# SCH_batcam10_2026-05-04.net
KiCad netlist of a schematic drawn in EasyEDA
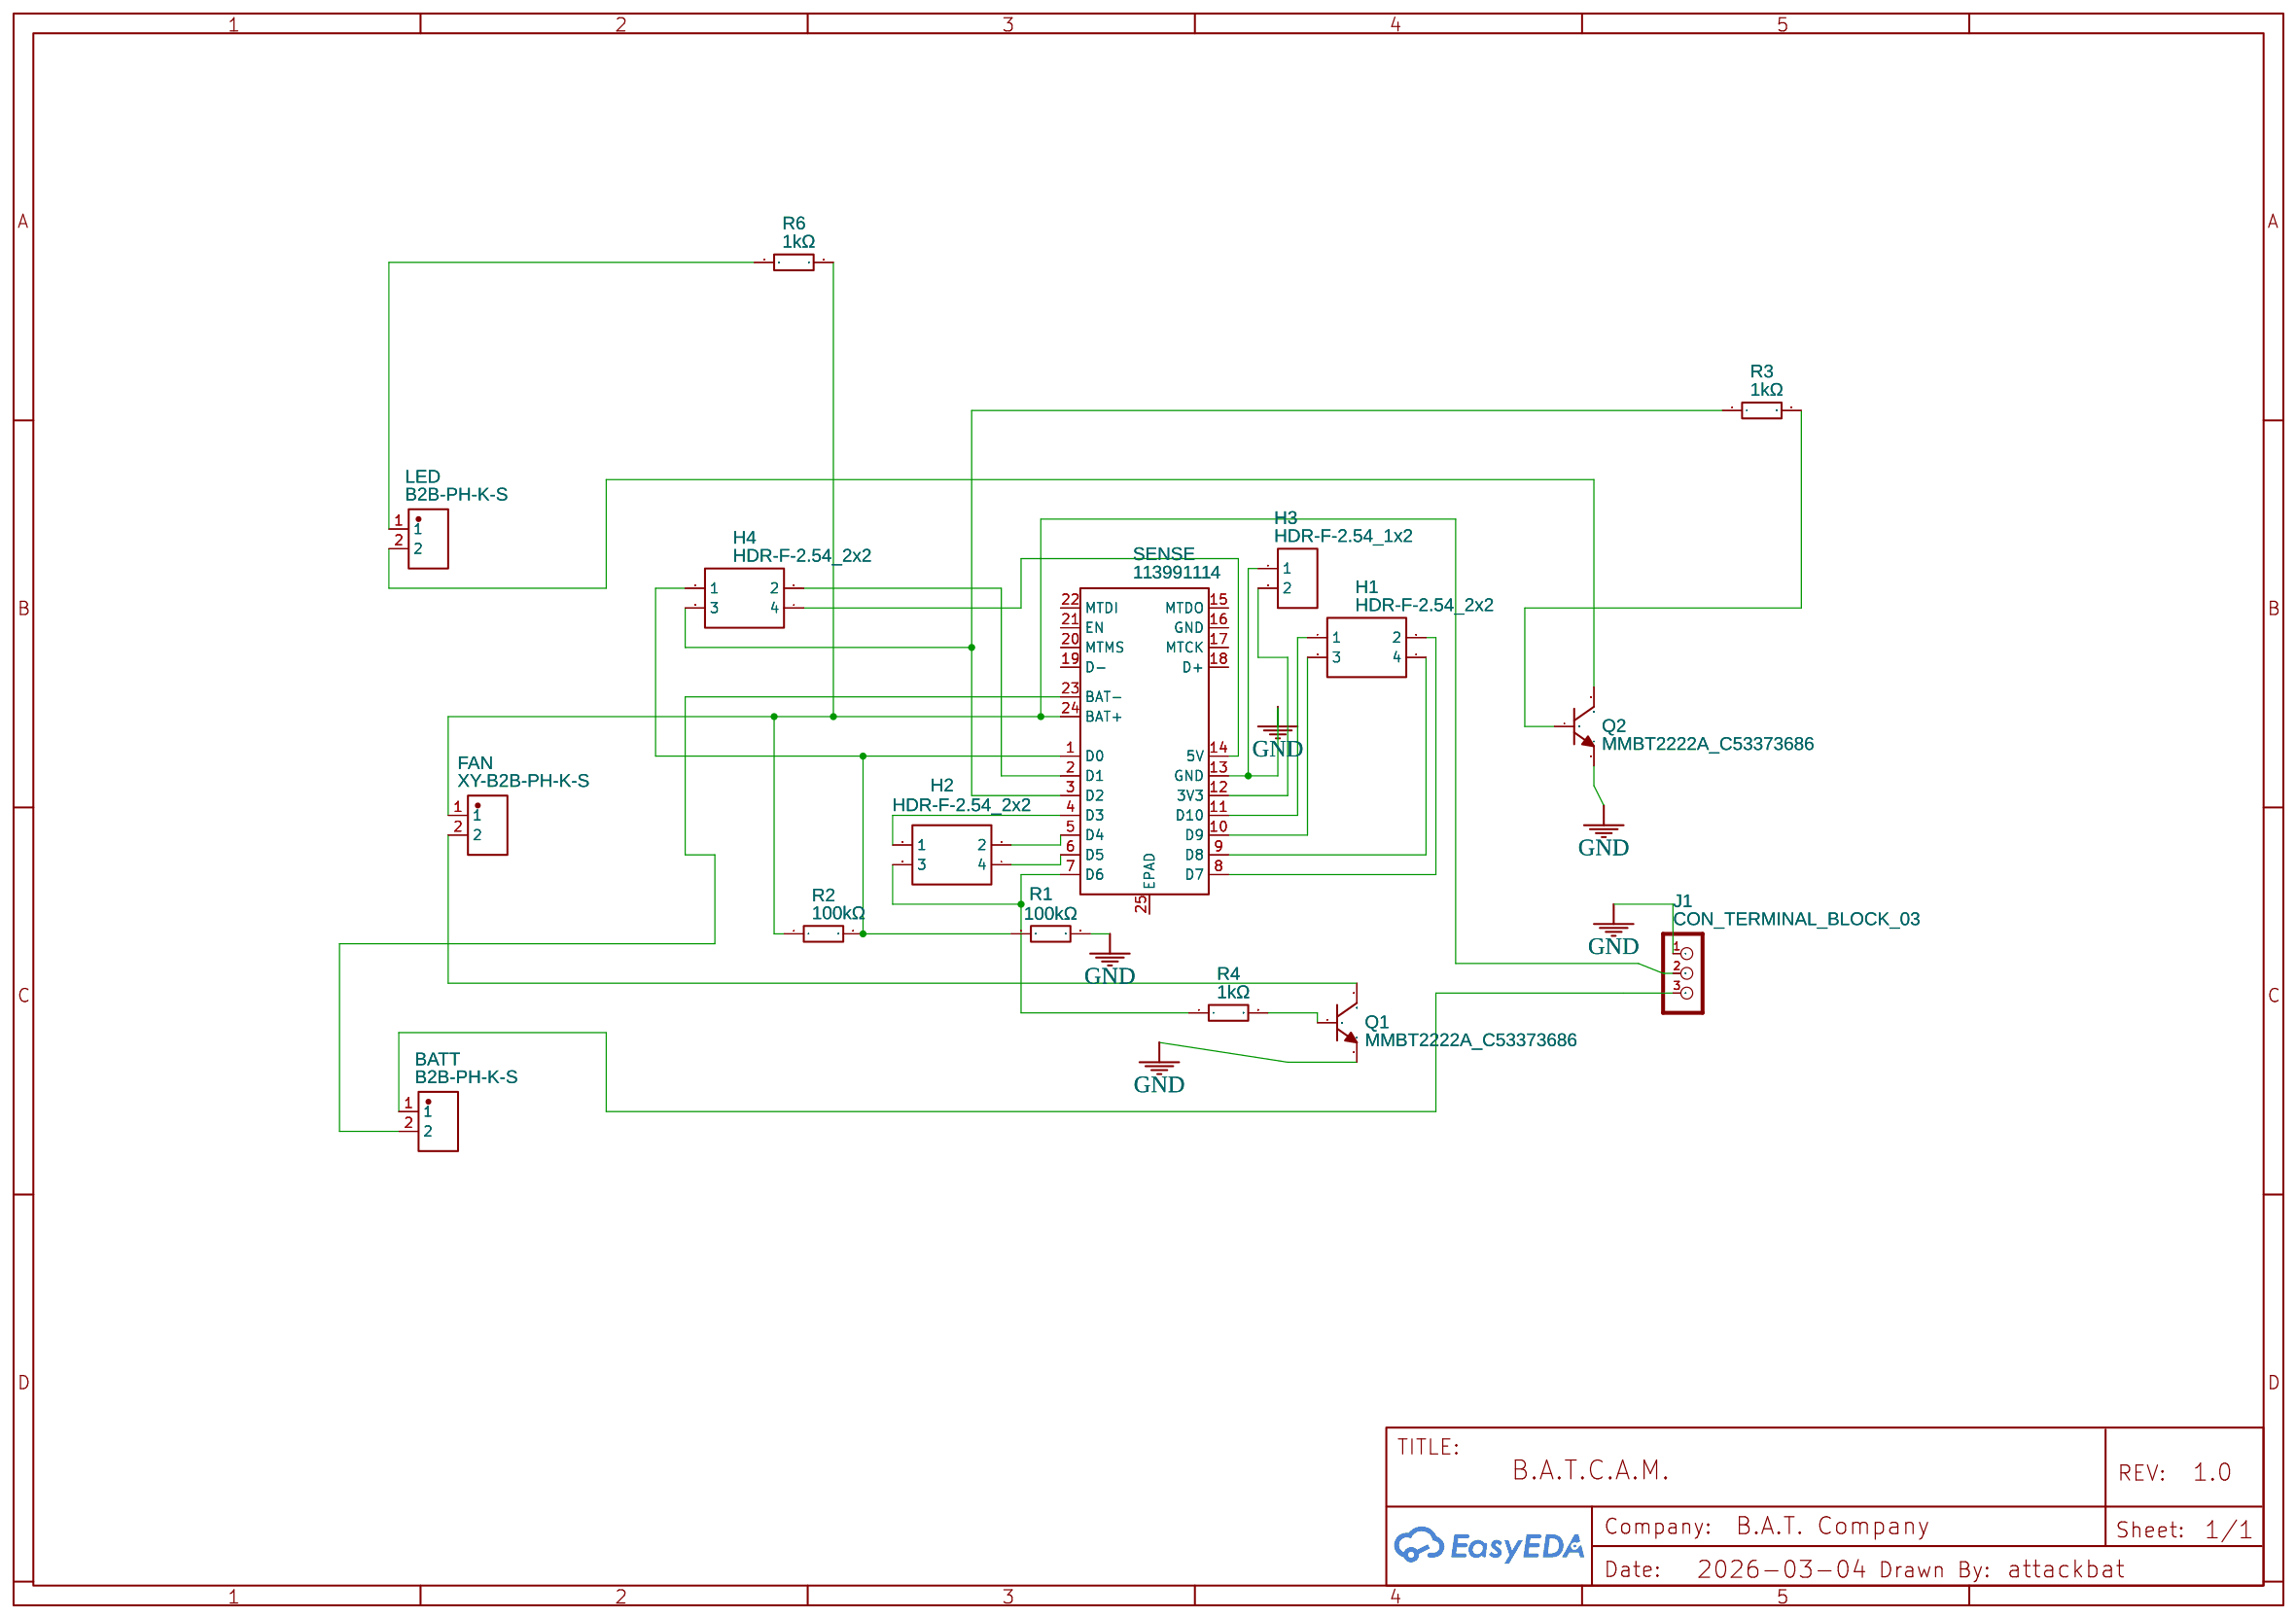
[diagram p0: schematic sheet]

(export (version "E")
  (design (tool "Eeschema 10.0.6"))
  (components
    (comp (ref "BATT")
      (value "B2B-PH-K-S")
      (fields (field (name "Manufacturer") "JST"))
      (libsource (lib "") (part "B2B-PH-K-S"))
    )
    (comp (ref "FAN")
      (value "XY-B2B-PH-K-S")
      (fields (field (name "Manufacturer") "XYECONN(辛译)"))
      (libsource (lib "") (part "XY-B2B-PH-K-S"))
    )
    (comp (ref "H1") (value "HDR-F-2.54_2x2") (libsource (lib "") (part "HDR-F-2.54_2x2")))
    (comp (ref "H2") (value "HDR-F-2.54_2x2") (libsource (lib "") (part "HDR-F-2.54_2x2")))
    (comp (ref "H3") (value "HDR-F-2.54_1x2") (libsource (lib "") (part "HDR-F-2.54_1x2")))
    (comp (ref "H4") (value "HDR-F-2.54_2x2") (libsource (lib "") (part "HDR-F-2.54_2x2")))
    (comp (ref "J1") (value "CON_TERMINAL_BLOCK_03") (libsource (lib "") (part "CON_TERMINAL_BLOCK_03")))
    (comp (ref "LED")
      (value "B2B-PH-K-S")
      (fields (field (name "Manufacturer") "JST"))
      (libsource (lib "") (part "B2B-PH-K-S_1"))
    )
    (comp (ref "Q1")
      (value "MMBT2222A_C53373686")
      (fields (field (name "Manufacturer Part") "MMBT2222A") (field (name "Manufacturer") "CCX(晁禾)"))
      (libsource (lib "") (part "MMBT2222A_C53373686"))
    )
    (comp (ref "Q2")
      (value "MMBT2222A_C53373686")
      (fields (field (name "Manufacturer Part") "MMBT2222A") (field (name "Manufacturer") "CCX(晁禾)"))
      (libsource (lib "") (part "MMBT2222A_C53373686"))
    )
    (comp (ref "R1")
      (value "100kΩ")
      (fields
        (field (name "Manufacturer Part") "0805W8F1003T5E")
        (field (name "Manufacturer") "UNI-ROYAL(厚声)")
      )
      (libsource (lib "") (part "0805W8F1003T5E_C149504"))
    )
    (comp (ref "R2")
      (value "100kΩ")
      (fields
        (field (name "Manufacturer Part") "0805W8F1003T5E")
        (field (name "Manufacturer") "UNI-ROYAL(厚声)")
      )
      (libsource (lib "") (part "0805W8F1003T5E_C149504"))
    )
    (comp (ref "R3")
      (value "1kΩ")
      (fields
        (field (name "Manufacturer Part") "0805W8F1001T5E")
        (field (name "Manufacturer") "UNI-ROYAL(厚声)")
      )
      (libsource (lib "") (part "0805W8F1001T5E"))
    )
    (comp (ref "R4")
      (value "1kΩ")
      (fields
        (field (name "Manufacturer Part") "0805W8F1001T5E")
        (field (name "Manufacturer") "UNI-ROYAL(厚声)")
      )
      (libsource (lib "") (part "0805W8F1001T5E"))
    )
    (comp (ref "R6")
      (value "1kΩ")
      (fields
        (field (name "Manufacturer Part") "0805W8F1001T5E")
        (field (name "Manufacturer") "UNI-ROYAL(厚声)")
      )
      (libsource (lib "") (part "0805W8F1001T5E"))
    )
    (comp (ref "SENSE")
      (value "113991114")
      (fields (field (name "Manufacturer") "Seeed(矽递科技)"))
      (libsource (lib "") (part "113991114"))
    )
  )
  (nets
    (net (code "1") (name "GND") (class "Default")
      (node (ref "H3") (pin "1") (pinfunction "1_1") (pintype "input"))
      (node (ref "J1") (pin "1") (pinfunction "1_1") (pintype "unspecified"))
      (node (ref "Q1") (pin "2") (pinfunction "E_2") (pintype "unspecified"))
      (node (ref "Q2") (pin "2") (pinfunction "E_2") (pintype "unspecified"))
      (node (ref "R1") (pin "2") (pinfunction "2_2") (pintype "unspecified"))
      (node (ref "SENSE") (pin "13") (pinfunction "GND_13") (pintype "unspecified"))
    )
    (net (code "2") (name "Net-(BATT-Pad1)") (class "Default")
      (node (ref "BATT") (pin "1") (pinfunction "1_1") (pintype "unspecified"))
      (node (ref "J1") (pin "3") (pinfunction "3_3") (pintype "unspecified"))
    )
    (net (code "3") (name "Net-(LED-Pad1)") (class "Default")
      (node (ref "LED") (pin "1") (pinfunction "1_1") (pintype "unspecified"))
      (node (ref "R6") (pin "1") (pinfunction "1_1") (pintype "input"))
    )
    (net (code "4") (name "Net-(Q1-B)") (class "Default")
      (node (ref "Q1") (pin "1") (pinfunction "B_1") (pintype "unspecified"))
      (node (ref "R4") (pin "2") (pinfunction "2_2") (pintype "input"))
    )
    (net (code "5") (name "Net-(Q1-C)") (class "Default")
      (node (ref "FAN") (pin "2") (pinfunction "2_2") (pintype "unspecified"))
      (node (ref "Q1") (pin "3") (pinfunction "C_3") (pintype "unspecified"))
    )
    (net (code "6") (name "Net-(Q2-B)") (class "Default")
      (node (ref "Q2") (pin "1") (pinfunction "B_1") (pintype "unspecified"))
      (node (ref "R3") (pin "2") (pinfunction "2_2") (pintype "input"))
    )
    (net (code "7") (name "Net-(Q2-C)") (class "Default")
      (node (ref "LED") (pin "2") (pinfunction "2_2") (pintype "unspecified"))
      (node (ref "Q2") (pin "3") (pinfunction "C_3") (pintype "unspecified"))
    )
    (net (code "8") (name "Net-(SENSE-3V3)") (class "Default")
      (node (ref "H3") (pin "2") (pinfunction "2_2") (pintype "input"))
      (node (ref "SENSE") (pin "12") (pinfunction "3V3_12") (pintype "unspecified"))
    )
    (net (code "9") (name "Net-(SENSE-5V)") (class "Default")
      (node (ref "H4") (pin "4") (pinfunction "4_4") (pintype "unspecified"))
      (node (ref "SENSE") (pin "14") (pinfunction "5V_14") (pintype "unspecified"))
    )
    (net (code "10") (name "Net-(SENSE-BAT+)") (class "Default")
      (node (ref "FAN") (pin "1") (pinfunction "1_1") (pintype "unspecified"))
      (node (ref "J1") (pin "2") (pinfunction "2_2") (pintype "unspecified"))
      (node (ref "R2") (pin "1") (pinfunction "1_1") (pintype "unspecified"))
      (node (ref "R6") (pin "2") (pinfunction "2_2") (pintype "input"))
      (node (ref "SENSE") (pin "24") (pinfunction "BAT+_24") (pintype "unspecified"))
    )
    (net (code "11") (name "Net-(SENSE-BAT-)") (class "Default")
      (node (ref "BATT") (pin "2") (pinfunction "2_2") (pintype "unspecified"))
      (node (ref "SENSE") (pin "23") (pinfunction "BAT-_23") (pintype "unspecified"))
    )
    (net (code "12") (name "Net-(SENSE-D0)") (class "Default")
      (node (ref "H4") (pin "1") (pinfunction "1_1") (pintype "unspecified"))
      (node (ref "R1") (pin "1") (pinfunction "1_1") (pintype "unspecified"))
      (node (ref "R2") (pin "2") (pinfunction "2_2") (pintype "unspecified"))
      (node (ref "SENSE") (pin "1") (pinfunction "D0_1") (pintype "unspecified"))
    )
    (net (code "13") (name "Net-(SENSE-D1)") (class "Default")
      (node (ref "H4") (pin "2") (pinfunction "2_2") (pintype "unspecified"))
      (node (ref "SENSE") (pin "2") (pinfunction "D1_2") (pintype "unspecified"))
    )
    (net (code "14") (name "Net-(SENSE-D2)") (class "Default")
      (node (ref "H4") (pin "3") (pinfunction "3_3") (pintype "unspecified"))
      (node (ref "R3") (pin "1") (pinfunction "1_1") (pintype "input"))
      (node (ref "SENSE") (pin "3") (pinfunction "D2_3") (pintype "unspecified"))
    )
    (net (code "15") (name "Net-(SENSE-D3)") (class "Default")
      (node (ref "H2") (pin "1") (pinfunction "1_1") (pintype "unspecified"))
      (node (ref "SENSE") (pin "4") (pinfunction "D3_4") (pintype "unspecified"))
    )
    (net (code "16") (name "Net-(SENSE-D4)") (class "Default")
      (node (ref "H2") (pin "2") (pinfunction "2_2") (pintype "unspecified"))
      (node (ref "SENSE") (pin "5") (pinfunction "D4_5") (pintype "unspecified"))
    )
    (net (code "17") (name "Net-(SENSE-D5)") (class "Default")
      (node (ref "H2") (pin "4") (pinfunction "4_4") (pintype "unspecified"))
      (node (ref "SENSE") (pin "6") (pinfunction "D5_6") (pintype "unspecified"))
    )
    (net (code "18") (name "Net-(SENSE-D6)") (class "Default")
      (node (ref "H2") (pin "3") (pinfunction "3_3") (pintype "unspecified"))
      (node (ref "R4") (pin "1") (pinfunction "1_1") (pintype "input"))
      (node (ref "SENSE") (pin "7") (pinfunction "D6_7") (pintype "unspecified"))
    )
    (net (code "19") (name "Net-(SENSE-D7)") (class "Default")
      (node (ref "H1") (pin "2") (pinfunction "2_2") (pintype "unspecified"))
      (node (ref "SENSE") (pin "8") (pinfunction "D7_8") (pintype "unspecified"))
    )
    (net (code "20") (name "Net-(SENSE-D8)") (class "Default")
      (node (ref "H1") (pin "4") (pinfunction "4_4") (pintype "unspecified"))
      (node (ref "SENSE") (pin "9") (pinfunction "D8_9") (pintype "unspecified"))
    )
    (net (code "21") (name "Net-(SENSE-D9)") (class "Default")
      (node (ref "H1") (pin "3") (pinfunction "3_3") (pintype "unspecified"))
      (node (ref "SENSE") (pin "10") (pinfunction "D9_10") (pintype "unspecified"))
    )
    (net (code "22") (name "Net-(SENSE-D10)") (class "Default")
      (node (ref "H1") (pin "1") (pinfunction "1_1") (pintype "unspecified"))
      (node (ref "SENSE") (pin "11") (pinfunction "D10_11") (pintype "unspecified"))
    )
    (net (code "23") (name "unconnected-(SENSE-D+-Pad18)") (class "Default")
      (node (ref "SENSE") (pin "18") (pinfunction "D+_18") (pintype "unspecified"))
    )
    (net (code "24") (name "unconnected-(SENSE-D--Pad19)") (class "Default")
      (node (ref "SENSE") (pin "19") (pinfunction "D-_19") (pintype "unspecified"))
    )
    (net (code "25") (name "unconnected-(SENSE-EN-Pad21)") (class "Default")
      (node (ref "SENSE") (pin "21") (pinfunction "EN_21") (pintype "unspecified"))
    )
    (net (code "26") (name "unconnected-(SENSE-EPAD-Pad25)") (class "Default")
      (node (ref "SENSE") (pin "25") (pinfunction "EPAD_25") (pintype "unspecified"))
    )
    (net (code "27") (name "unconnected-(SENSE-GND-Pad16)") (class "Default")
      (node (ref "SENSE") (pin "16") (pinfunction "GND_16") (pintype "unspecified"))
    )
    (net (code "28") (name "unconnected-(SENSE-MTCK-Pad17)") (class "Default")
      (node (ref "SENSE") (pin "17") (pinfunction "MTCK_17") (pintype "unspecified"))
    )
    (net (code "29") (name "unconnected-(SENSE-MTDI-Pad22)") (class "Default")
      (node (ref "SENSE") (pin "22") (pinfunction "MTDI_22") (pintype "unspecified"))
    )
    (net (code "30") (name "unconnected-(SENSE-MTDO-Pad15)") (class "Default")
      (node (ref "SENSE") (pin "15") (pinfunction "MTDO_15") (pintype "unspecified"))
    )
    (net (code "31") (name "unconnected-(SENSE-MTMS-Pad20)") (class "Default")
      (node (ref "SENSE") (pin "20") (pinfunction "MTMS_20") (pintype "unspecified"))
    )
  )
)
